# 08-Power_3V3.net
KiCad netlist of a schematic drawn in Altium Designer
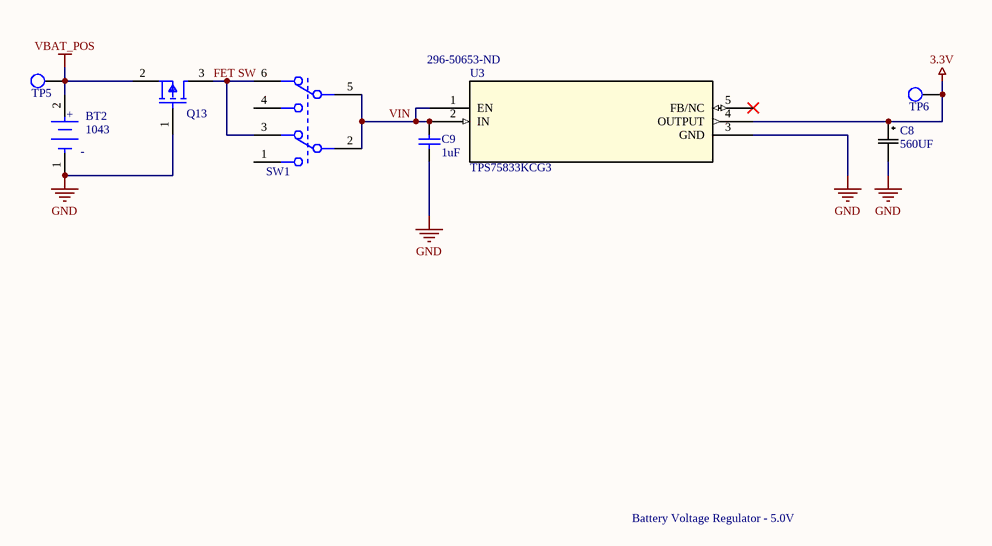
[diagram p0: 08-Power_3V3.SchDoc]

(export (version "E")
  (design (tool "Eeschema 10.0.6"))
  (components
    (comp (ref "BT2")
      (value "1043")
      (footprint "Keystone_1043_0")
      (description "Cylindrical Battery Contacts, Clips, Holders & Springs 18650 PCB PLASTIC BATT HLDR THM 1 CELL")
      (fields (field (name "MANUFACTURER PART NUMBER 1") "1043"))
      (libsource (lib "Battery") (part "1043"))
    )
    (comp (ref "C8")
      (value "560UF")
      (footprint "CAP_RHA/HS_8X7P7_NCH")
      (description "CAP ALUM POLY 560UF 20% 6.3V SMD")
      (fields
        (field (name "MANUFACTURER_PART_NUMBER") "RHA0J561MCN1GS")
        (field (name "COPYRIGHT") "Copyright (C) 2022 Ultra Librarian. All rights reserved.")
      )
      (libsource (lib "team6") (part "RHA0J561MCN1GS"))
    )
    (comp (ref "C9")
      (value "1uF")
      (footprint "CAPC2013X145X50LL20T25")
      (fields (field (name "MANUFACTURER") "Kemet") (field (name "PART NUMBER") "C0805C105K4PACTU"))
      (libsource (lib "Altium Content Vault") (part "CAP"))
    )
    (comp (ref "Q13")
      (value "SSM3J328R,LF")
      (footprint "SOT-23_M")
      (description "MOSFET P-CH 20V 6A SOT23F")
      (libsource (lib "Transistors") (part "SSM3J328R,LF"))
    )
    (comp (ref "SW1")
      (value "JS202011SCQN")
      (footprint "C&K_Components_0_MFG")
      (description "C & K COMPONENTS - JS202011SCQN - SWITCH, DPDT, 0.6A, 6VDC, SMD")
      (libsource (lib "Switches") (part "JS202011SCQN"))
    )
    (comp (ref "TP5")
      (value "TP_1206")
      (footprint "TP-SMC-1206")
      (description "Test Point SMD 1206")
      (fields
        (field (name "MANUFACTURER") "TE Connectivity (Tyco Electronics)")
        (field (name "MANUFACTURER PART NUMBER") "1625854-1")
      )
      (libsource (lib "Mechanical") (part "TP_1206"))
    )
    (comp (ref "TP6")
      (value "TP_1206")
      (footprint "TP-SMC-1206")
      (description "Test Point SMD 1206")
      (fields
        (field (name "MANUFACTURER") "TE Connectivity (Tyco Electronics)")
        (field (name "MANUFACTURER PART NUMBER") "1625854-1")
      )
      (libsource (lib "Mechanical") (part "TP_1206"))
    )
    (comp (ref "U3")
      (value "TPS75833KCG3")
      (footprint "KC5")
      (description "IC REG LINEAR 3.3V 3A TO220-5")
      (fields
        (field (name "SUPPLIER PART NUMBER 1") "296-50653-ND")
        (field (name "COPYRIGHT") "Copyright (C) 2022 Ultra Librarian. All rights reserved.")
      )
      (libsource (lib "team6") (part "TPS75833KCG3"))
    )
  )
  (nets
    (net (code "1") (name "/FET SW") (class "Default")
      (node (ref "Q13") (pin "3") (pinfunction "Drain_3") (pintype "passive"))
      (node (ref "SW1") (pin "3") (pinfunction "3_3") (pintype "passive"))
      (node (ref "SW1") (pin "6") (pinfunction "6_6") (pintype "passive"))
    )
    (net (code "2") (name "/VIN") (class "Default")
      (node (ref "C9") (pin "1") (pinfunction "1_1") (pintype "passive"))
      (node (ref "SW1") (pin "2") (pinfunction "2_2") (pintype "passive"))
      (node (ref "SW1") (pin "5") (pinfunction "5_5") (pintype "passive"))
      (node (ref "U3") (pin "1") (pinfunction "EN_1") (pintype "passive"))
      (node (ref "U3") (pin "2") (pinfunction "IN_2") (pintype "input"))
    )
    (net (code "3") (name "3.3V") (class "Default")
      (node (ref "C8") (pin "1") (pinfunction "1_1") (pintype "passive"))
      (node (ref "TP6") (pin "1") (pintype "passive"))
      (node (ref "U3") (pin "4") (pinfunction "OUTPUT_4") (pintype "output"))
    )
    (net (code "4") (name "GND") (class "Default")
      (node (ref "BT2") (pin "1") (pinfunction "C_1") (pintype "passive"))
      (node (ref "C8") (pin "2") (pinfunction "2_2") (pintype "passive"))
      (node (ref "C9") (pin "2") (pinfunction "2_2") (pintype "passive"))
      (node (ref "Q13") (pin "1") (pinfunction "Gate_1") (pintype "passive"))
      (node (ref "U3") (pin "3") (pinfunction "GND_3") (pintype "power_in"))
    )
    (net (code "5") (name "VBAT_POS") (class "Default")
      (node (ref "BT2") (pin "2") (pinfunction "A_2") (pintype "passive"))
      (node (ref "Q13") (pin "2") (pinfunction "Source_2") (pintype "passive"))
      (node (ref "TP5") (pin "1") (pintype "passive"))
    )
    (net (code "6") (name "unconnected-(SW1-Pad1)") (class "Default")
      (node (ref "SW1") (pin "1") (pinfunction "1_1") (pintype "passive"))
    )
    (net (code "7") (name "unconnected-(SW1-Pad4)") (class "Default")
      (node (ref "SW1") (pin "4") (pinfunction "4_4") (pintype "passive"))
    )
    (net (code "8") (name "unconnected-(U3-FB{slash}NC-Pad5)") (class "Default")
      (node (ref "U3") (pin "5") (pinfunction "FB/NC_5") (pintype "bidirectional+no_connect"))
    )
  )
)
